# Camera-MT_Sch.net
KiCad netlist of a schematic drawn in Altium Designer
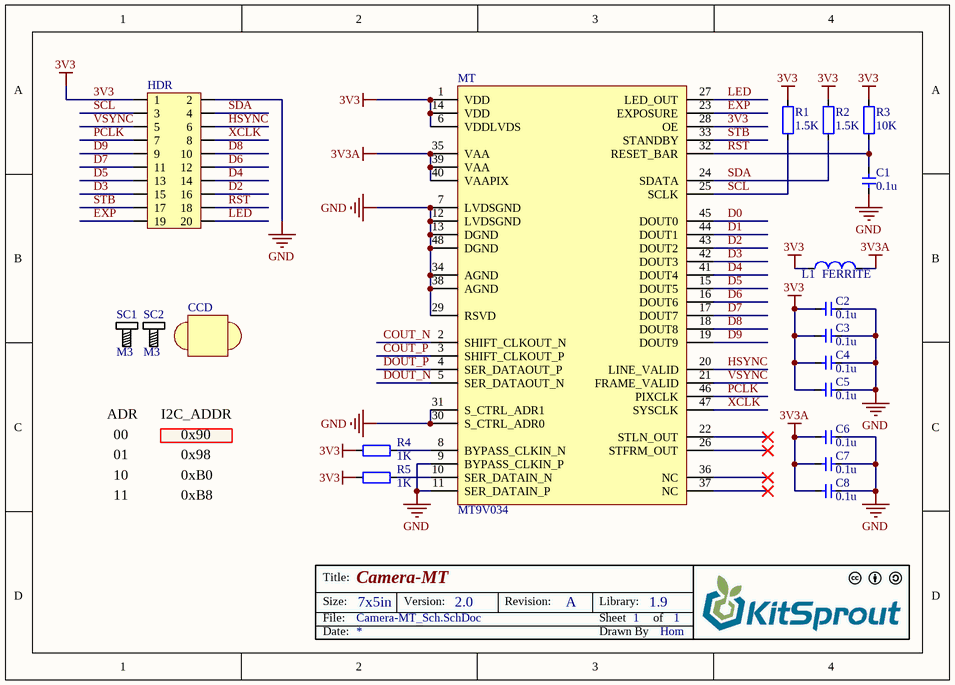
[diagram p0: Camera-MT_Sch.SchDoc]

(export (version "E")
  (design (tool "Eeschema 10.0.6"))
  (components
    (comp (ref "C1")
      (value "0.1u")
      (footprint "PCB_PassiveCap:CAP_0603")
      (description "Capacitor")
      (fields (field (name "Comment") "Cap_0603"))
      (libsource (lib "SCH_Passive") (part "Cap_0603"))
    )
    (comp (ref "C2")
      (value "0.1u")
      (footprint "PCB_PassiveCap:CAP_0603")
      (description "Capacitor")
      (fields (field (name "Comment") "Cap_0603"))
      (libsource (lib "SCH_Passive") (part "Cap_0603"))
    )
    (comp (ref "C3")
      (value "0.1u")
      (footprint "PCB_PassiveCap:CAP_0402")
      (description "Capacitor")
      (fields (field (name "Comment") "Cap_0402"))
      (libsource (lib "SCH_Passive") (part "Cap_0402"))
    )
    (comp (ref "C4")
      (value "0.1u")
      (footprint "PCB_PassiveCap:CAP_0603")
      (description "Capacitor")
      (fields (field (name "Comment") "Cap_0603"))
      (libsource (lib "SCH_Passive") (part "Cap_0603"))
    )
    (comp (ref "C5")
      (value "0.1u")
      (footprint "PCB_PassiveCap:CAP_0603")
      (description "Capacitor")
      (fields (field (name "Comment") "Cap_0603"))
      (libsource (lib "SCH_Passive") (part "Cap_0603"))
    )
    (comp (ref "C6")
      (value "0.1u")
      (footprint "PCB_PassiveCap:CAP_0603")
      (description "Capacitor")
      (fields (field (name "Comment") "Cap_0603"))
      (libsource (lib "SCH_Passive") (part "Cap_0603"))
    )
    (comp (ref "C7")
      (value "0.1u")
      (footprint "PCB_PassiveCap:CAP_0603")
      (description "Capacitor")
      (fields (field (name "Comment") "Cap_0603"))
      (libsource (lib "SCH_Passive") (part "Cap_0603"))
    )
    (comp (ref "C8")
      (value "0.1u")
      (footprint "PCB_PassiveCap:CAP_0603")
      (description "Capacitor")
      (fields (field (name "Comment") "Cap_0603"))
      (libsource (lib "SCH_Passive") (part "Cap_0603"))
    )
    (comp (ref "CCD")
      (value "CCD")
      (footprint "PCB_Mechanical:CCD_LENS_20MM")
      (libsource (lib "SCH_Mechanical") (part "lensCCD_20"))
    )
    (comp (ref "HDR")
      (value "HDR2x10_2.54")
      (footprint "PCB_ConnectorHDR:HDR2X10_2.54_180")
      (description "Header")
      (libsource (lib "SCH_ConnectorHDR") (part "HDR2x10_2.54"))
    )
    (comp (ref "L1")
      (value "FERRITE")
      (footprint "PCB_PassiveInd:IND_0603")
      (description "Inductor")
      (fields (field (name "Comment") "Ind_0603"))
      (libsource (lib "SCH_Passive") (part "Ind_0603"))
    )
    (comp (ref "MT")
      (value "MT9V034")
      (footprint "PCB_IntegratedCircuit:CLCC_48")
      (description "CMOS")
      (libsource (lib "SCH_IntegratedCircuit") (part "MT9V034"))
    )
    (comp (ref "R1")
      (value "1.5K")
      (footprint "PCB_PassiveRes:RES_0603")
      (description "Resistor")
      (fields (field (name "Comment") "Res_0603"))
      (libsource (lib "SCH_Passive") (part "Res_0603"))
    )
    (comp (ref "R2")
      (value "1.5K")
      (footprint "PCB_PassiveRes:RES_0603")
      (description "Resistor")
      (fields (field (name "Comment") "Res_0603"))
      (libsource (lib "SCH_Passive") (part "Res_0603"))
    )
    (comp (ref "R3")
      (value "10K")
      (footprint "PCB_PassiveRes:RES_0603")
      (description "Resistor")
      (fields (field (name "Comment") "Res_0603"))
      (libsource (lib "SCH_Passive") (part "Res_0603"))
    )
    (comp (ref "R4")
      (value "1K")
      (footprint "PCB_PassiveRes:RES_0603")
      (description "Resistor")
      (fields (field (name "Comment") "Res_0603"))
      (libsource (lib "") (part "Res_0603_1"))
    )
    (comp (ref "R5")
      (value "1K")
      (footprint "PCB_PassiveRes:RES_0603")
      (description "Resistor")
      (fields (field (name "Comment") "Res_0603"))
      (libsource (lib "") (part "Res_0603_1"))
    )
    (comp (ref "SC1")
      (value "M3")
      (footprint "PCB_Mechanical:SCRREW_M3")
      (description "Screw")
      (libsource (lib "SCH_Mechanical") (part "Screw_M3"))
    )
    (comp (ref "SC2")
      (value "M3")
      (footprint "PCB_Mechanical:SCRREW_M3")
      (description "Screw")
      (libsource (lib "SCH_Mechanical") (part "Screw_M3"))
    )
  )
  (nets
    (net (code "1") (name "/COUT_N") (class "Default")
      (node (ref "MT") (pin "2") (pinfunction "SHIFT_CLKOUT_N_2") (pintype "passive"))
    )
    (net (code "2") (name "/COUT_P") (class "Default")
      (node (ref "MT") (pin "3") (pinfunction "SHIFT_CLKOUT_P_3") (pintype "passive"))
    )
    (net (code "3") (name "/D0") (class "Default")
      (node (ref "MT") (pin "45") (pinfunction "DOUT0_45") (pintype "passive"))
    )
    (net (code "4") (name "/D1") (class "Default")
      (node (ref "MT") (pin "44") (pinfunction "DOUT1_44") (pintype "passive"))
    )
    (net (code "5") (name "/D2") (class "Default")
      (node (ref "HDR") (pin "16") (pinfunction "16_16") (pintype "passive"))
      (node (ref "MT") (pin "43") (pinfunction "DOUT2_43") (pintype "passive"))
    )
    (net (code "6") (name "/D3") (class "Default")
      (node (ref "HDR") (pin "15") (pinfunction "15_15") (pintype "passive"))
      (node (ref "MT") (pin "42") (pinfunction "DOUT3_42") (pintype "passive"))
    )
    (net (code "7") (name "/D4") (class "Default")
      (node (ref "HDR") (pin "14") (pinfunction "14_14") (pintype "passive"))
      (node (ref "MT") (pin "41") (pinfunction "DOUT4_41") (pintype "passive"))
    )
    (net (code "8") (name "/D5") (class "Default")
      (node (ref "HDR") (pin "13") (pinfunction "13_13") (pintype "passive"))
      (node (ref "MT") (pin "15") (pinfunction "DOUT5_15") (pintype "passive"))
    )
    (net (code "9") (name "/D6") (class "Default")
      (node (ref "HDR") (pin "12") (pinfunction "12_12") (pintype "passive"))
      (node (ref "MT") (pin "16") (pinfunction "DOUT6_16") (pintype "passive"))
    )
    (net (code "10") (name "/D7") (class "Default")
      (node (ref "HDR") (pin "11") (pinfunction "11_11") (pintype "passive"))
      (node (ref "MT") (pin "17") (pinfunction "DOUT7_17") (pintype "passive"))
    )
    (net (code "11") (name "/D8") (class "Default")
      (node (ref "HDR") (pin "10") (pinfunction "10_10") (pintype "passive"))
      (node (ref "MT") (pin "18") (pinfunction "DOUT8_18") (pintype "passive"))
    )
    (net (code "12") (name "/D9") (class "Default")
      (node (ref "HDR") (pin "9") (pinfunction "9_9") (pintype "passive"))
      (node (ref "MT") (pin "19") (pinfunction "DOUT9_19") (pintype "passive"))
    )
    (net (code "13") (name "/DOUT_N") (class "Default")
      (node (ref "MT") (pin "5") (pinfunction "SER_DATAOUT_N_5") (pintype "passive"))
    )
    (net (code "14") (name "/DOUT_P") (class "Default")
      (node (ref "MT") (pin "4") (pinfunction "SER_DATAOUT_P_4") (pintype "passive"))
    )
    (net (code "15") (name "/EXP") (class "Default")
      (node (ref "HDR") (pin "19") (pinfunction "19_19") (pintype "passive"))
      (node (ref "MT") (pin "23") (pinfunction "EXPOSURE_23") (pintype "passive"))
    )
    (net (code "16") (name "/HSYNC") (class "Default")
      (node (ref "HDR") (pin "6") (pinfunction "6_6") (pintype "passive"))
      (node (ref "MT") (pin "20") (pinfunction "LINE_VALID_20") (pintype "passive"))
    )
    (net (code "17") (name "/LED") (class "Default")
      (node (ref "HDR") (pin "20") (pinfunction "20_20") (pintype "passive"))
      (node (ref "MT") (pin "27") (pinfunction "LED_OUT_27") (pintype "passive"))
    )
    (net (code "18") (name "/PCLK") (class "Default")
      (node (ref "HDR") (pin "7") (pinfunction "7_7") (pintype "passive"))
      (node (ref "MT") (pin "46") (pinfunction "PIXCLK_46") (pintype "passive"))
    )
    (net (code "19") (name "/RST") (class "Default")
      (node (ref "C1") (pin "2") (pinfunction "2_2") (pintype "passive"))
      (node (ref "HDR") (pin "18") (pinfunction "18_18") (pintype "passive"))
      (node (ref "MT") (pin "32") (pinfunction "RESET_BAR_32") (pintype "passive"))
      (node (ref "R3") (pin "1") (pinfunction "1_1") (pintype "passive"))
    )
    (net (code "20") (name "/SCL") (class "Default")
      (node (ref "HDR") (pin "3") (pinfunction "3_3") (pintype "passive"))
      (node (ref "MT") (pin "25") (pinfunction "SCLK_25") (pintype "passive"))
      (node (ref "R1") (pin "1") (pinfunction "1_1") (pintype "passive"))
    )
    (net (code "21") (name "/SDA") (class "Default")
      (node (ref "HDR") (pin "4") (pinfunction "4_4") (pintype "passive"))
      (node (ref "MT") (pin "24") (pinfunction "SDATA_24") (pintype "passive"))
      (node (ref "R2") (pin "1") (pinfunction "1_1") (pintype "passive"))
    )
    (net (code "22") (name "/STB") (class "Default")
      (node (ref "HDR") (pin "17") (pinfunction "17_17") (pintype "passive"))
      (node (ref "MT") (pin "33") (pinfunction "STANDBY_33") (pintype "passive"))
    )
    (net (code "23") (name "/VSYNC") (class "Default")
      (node (ref "HDR") (pin "5") (pinfunction "5_5") (pintype "passive"))
      (node (ref "MT") (pin "21") (pinfunction "FRAME_VALID_21") (pintype "passive"))
    )
    (net (code "24") (name "/XCLK") (class "Default")
      (node (ref "HDR") (pin "8") (pinfunction "8_8") (pintype "passive"))
      (node (ref "MT") (pin "47") (pinfunction "SYSCLK_47") (pintype "passive"))
    )
    (net (code "25") (name "3V3") (class "Default")
      (node (ref "C2") (pin "2") (pinfunction "2_2") (pintype "passive"))
      (node (ref "C3") (pin "2") (pinfunction "2_2") (pintype "passive"))
      (node (ref "C4") (pin "2") (pinfunction "2_2") (pintype "passive"))
      (node (ref "C5") (pin "2") (pinfunction "2_2") (pintype "passive"))
      (node (ref "HDR") (pin "1") (pinfunction "1_1") (pintype "passive"))
      (node (ref "L1") (pin "1") (pinfunction "1_1") (pintype "passive"))
      (node (ref "MT") (pin "1") (pinfunction "VDD_1") (pintype "passive"))
      (node (ref "MT") (pin "14") (pinfunction "VDD_14") (pintype "passive"))
      (node (ref "MT") (pin "28") (pinfunction "OE_28") (pintype "passive"))
      (node (ref "MT") (pin "6") (pinfunction "VDDLVDS_6") (pintype "passive"))
      (node (ref "R1") (pin "2") (pinfunction "2_2") (pintype "passive"))
      (node (ref "R2") (pin "2") (pinfunction "2_2") (pintype "passive"))
      (node (ref "R3") (pin "2") (pinfunction "2_2") (pintype "passive"))
      (node (ref "R4") (pin "2") (pinfunction "2_2") (pintype "passive"))
      (node (ref "R5") (pin "2") (pinfunction "2_2") (pintype "passive"))
    )
    (net (code "26") (name "3V3A") (class "Default")
      (node (ref "C6") (pin "2") (pinfunction "2_2") (pintype "passive"))
      (node (ref "C7") (pin "2") (pinfunction "2_2") (pintype "passive"))
      (node (ref "C8") (pin "2") (pinfunction "2_2") (pintype "passive"))
      (node (ref "L1") (pin "2") (pinfunction "2_2") (pintype "passive"))
      (node (ref "MT") (pin "35") (pinfunction "VAA_35") (pintype "passive"))
      (node (ref "MT") (pin "39") (pinfunction "VAA_39") (pintype "passive"))
      (node (ref "MT") (pin "40") (pinfunction "VAAPIX_40") (pintype "passive"))
    )
    (net (code "27") (name "GND") (class "Default")
      (node (ref "C1") (pin "1") (pinfunction "1_1") (pintype "passive"))
      (node (ref "C2") (pin "1") (pinfunction "1_1") (pintype "passive"))
      (node (ref "C3") (pin "1") (pinfunction "1_1") (pintype "passive"))
      (node (ref "C4") (pin "1") (pinfunction "1_1") (pintype "passive"))
      (node (ref "C5") (pin "1") (pinfunction "1_1") (pintype "passive"))
      (node (ref "C6") (pin "1") (pinfunction "1_1") (pintype "passive"))
      (node (ref "C7") (pin "1") (pinfunction "1_1") (pintype "passive"))
      (node (ref "C8") (pin "1") (pinfunction "1_1") (pintype "passive"))
      (node (ref "HDR") (pin "2") (pinfunction "2_2") (pintype "passive"))
      (node (ref "MT") (pin "11") (pinfunction "SER_DATAIN_P_11") (pintype "passive"))
      (node (ref "MT") (pin "12") (pinfunction "LVDSGND_12") (pintype "passive"))
      (node (ref "MT") (pin "13") (pinfunction "DGND_13") (pintype "passive"))
      (node (ref "MT") (pin "29") (pinfunction "RSVD_29") (pintype "passive"))
      (node (ref "MT") (pin "30") (pinfunction "S_CTRL_ADR0_30") (pintype "passive"))
      (node (ref "MT") (pin "31") (pinfunction "S_CTRL_ADR1_31") (pintype "passive"))
      (node (ref "MT") (pin "34") (pinfunction "AGND_34") (pintype "passive"))
      (node (ref "MT") (pin "38") (pinfunction "AGND_38") (pintype "passive"))
      (node (ref "MT") (pin "48") (pinfunction "DGND_48") (pintype "passive"))
      (node (ref "MT") (pin "7") (pinfunction "LVDSGND_7") (pintype "passive"))
      (node (ref "MT") (pin "9") (pinfunction "BYPASS_CLKIN_P_9") (pintype "passive"))
    )
    (net (code "28") (name "Net-(MT-BYPASS_CLKIN_N)") (class "Default")
      (node (ref "MT") (pin "8") (pinfunction "BYPASS_CLKIN_N_8") (pintype "passive"))
      (node (ref "R4") (pin "1") (pinfunction "1_1") (pintype "passive"))
    )
    (net (code "29") (name "Net-(MT-SER_DATAIN_N)") (class "Default")
      (node (ref "MT") (pin "10") (pinfunction "SER_DATAIN_N_10") (pintype "passive"))
      (node (ref "R5") (pin "1") (pinfunction "1_1") (pintype "passive"))
    )
    (net (code "30") (name "unconnected-(MT-NC-Pad36)") (class "Default")
      (node (ref "MT") (pin "36") (pinfunction "NC_36") (pintype "passive+no_connect"))
    )
    (net (code "31") (name "unconnected-(MT-NC-Pad37)") (class "Default")
      (node (ref "MT") (pin "37") (pinfunction "NC_37") (pintype "passive+no_connect"))
    )
    (net (code "32") (name "unconnected-(MT-STFRM_OUT-Pad26)") (class "Default")
      (node (ref "MT") (pin "26") (pinfunction "STFRM_OUT_26") (pintype "passive+no_connect"))
    )
    (net (code "33") (name "unconnected-(MT-STLN_OUT-Pad22)") (class "Default")
      (node (ref "MT") (pin "22") (pinfunction "STLN_OUT_22") (pintype "passive+no_connect"))
    )
  )
)
